# a-star_dual_drv8801_stapler.net
KiCad netlist of a schematic drawn in EAGLE
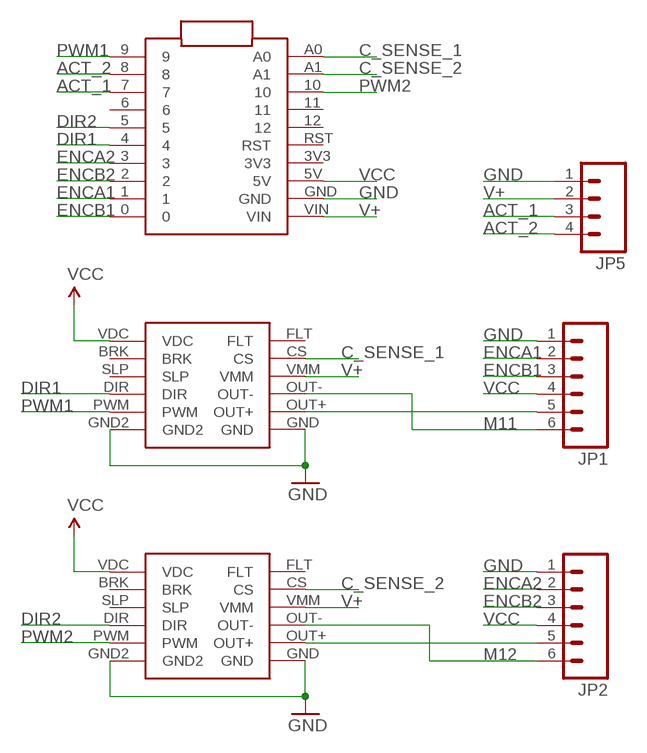
[diagram p0: schematic, sheet 1]

(export (version "E")
  (design (tool "Eeschema 10.0.6"))
  (components
    (comp (ref "JP1")
      (value "M06POLAR")
      (footprint "eagle-import:MOLEX-1X6")
      (libsource (lib "eagle-import") (part "M06POLAR"))
    )
    (comp (ref "JP2")
      (value "M06POLAR")
      (footprint "eagle-import:MOLEX-1X6")
      (libsource (lib "eagle-import") (part "M06POLAR"))
    )
    (comp (ref "JP5")
      (value "M04POLAR")
      (footprint "eagle-import:MOLEX-1X4")
      (libsource (lib "eagle-import") (part "M04POLAR"))
    )
    (comp (ref "U$1")
      (value "POLOLU_DRV8801_CARRIER")
      (footprint "eagle-import:POLOLU_DRV8801_CARRIER")
      (libsource (lib "eagle-import") (part "POLOLU_DRV8801_CARRIER"))
    )
    (comp (ref "U$2")
      (value "POLOLU_A-STAR-MICRO")
      (footprint "eagle-import:POLOLU_A-STAR-MICRO")
      (libsource (lib "eagle-import") (part "POLOLU_A-STAR-MICRO"))
    )
    (comp (ref "U$3")
      (value "POLOLU_DRV8801_CARRIER")
      (footprint "eagle-import:POLOLU_DRV8801_CARRIER")
      (libsource (lib "eagle-import") (part "POLOLU_DRV8801_CARRIER"))
    )
  )
  (nets
    (net (code "1") (name "/ACT_1") (class "Default")
      (node (ref "JP5") (pin "3") (pinfunction "3_3") (pintype "passive"))
      (node (ref "U$2") (pin "7") (pinfunction "7_7") (pintype "bidirectional"))
    )
    (net (code "2") (name "/ACT_2") (class "Default")
      (node (ref "JP5") (pin "4") (pinfunction "4_4") (pintype "passive"))
      (node (ref "U$2") (pin "8") (pinfunction "8_8") (pintype "bidirectional"))
    )
    (net (code "3") (name "/C_SENSE_1") (class "Default")
      (node (ref "U$1") (pin "CS") (pinfunction "CS_CS") (pintype "bidirectional"))
      (node (ref "U$2") (pin "A0") (pinfunction "A0_A0") (pintype "bidirectional"))
    )
    (net (code "4") (name "/C_SENSE_2") (class "Default")
      (node (ref "U$2") (pin "A1") (pinfunction "A1_A1") (pintype "bidirectional"))
      (node (ref "U$3") (pin "CS") (pinfunction "CS_CS") (pintype "bidirectional"))
    )
    (net (code "5") (name "/DIR1") (class "Default")
      (node (ref "U$1") (pin "DIR") (pinfunction "DIR_DIR") (pintype "bidirectional"))
      (node (ref "U$2") (pin "4") (pinfunction "4_4") (pintype "bidirectional"))
    )
    (net (code "6") (name "/DIR2") (class "Default")
      (node (ref "U$2") (pin "5") (pinfunction "5_5") (pintype "bidirectional"))
      (node (ref "U$3") (pin "DIR") (pinfunction "DIR_DIR") (pintype "bidirectional"))
    )
    (net (code "7") (name "/ENCA1") (class "Default")
      (node (ref "JP1") (pin "2") (pinfunction "2_2") (pintype "passive"))
      (node (ref "U$2") (pin "1") (pinfunction "1_1") (pintype "bidirectional"))
    )
    (net (code "8") (name "/ENCA2") (class "Default")
      (node (ref "JP2") (pin "2") (pinfunction "2_2") (pintype "passive"))
      (node (ref "U$2") (pin "3") (pinfunction "3_3") (pintype "bidirectional"))
    )
    (net (code "9") (name "/ENCB1") (class "Default")
      (node (ref "JP1") (pin "3") (pinfunction "3_3") (pintype "passive"))
      (node (ref "U$2") (pin "0") (pinfunction "0_0") (pintype "bidirectional"))
    )
    (net (code "10") (name "/ENCB2") (class "Default")
      (node (ref "JP2") (pin "3") (pinfunction "3_3") (pintype "passive"))
      (node (ref "U$2") (pin "2") (pinfunction "2_2") (pintype "bidirectional"))
    )
    (net (code "11") (name "/M11") (class "Default")
      (node (ref "JP1") (pin "6") (pinfunction "6_6") (pintype "passive"))
      (node (ref "U$1") (pin "OUT-") (pinfunction "OUT-_OUT-") (pintype "bidirectional"))
    )
    (net (code "12") (name "/M12") (class "Default")
      (node (ref "JP2") (pin "6") (pinfunction "6_6") (pintype "passive"))
      (node (ref "U$3") (pin "OUT-") (pinfunction "OUT-_OUT-") (pintype "bidirectional"))
    )
    (net (code "13") (name "/PWM1") (class "Default")
      (node (ref "U$1") (pin "PWM") (pinfunction "PWM_PWM") (pintype "bidirectional"))
      (node (ref "U$2") (pin "9") (pinfunction "9_9") (pintype "bidirectional"))
    )
    (net (code "14") (name "/PWM2") (class "Default")
      (node (ref "U$2") (pin "10") (pinfunction "10_10") (pintype "bidirectional"))
      (node (ref "U$3") (pin "PWM") (pinfunction "PWM_PWM") (pintype "bidirectional"))
    )
    (net (code "15") (name "/V+") (class "Default")
      (node (ref "JP5") (pin "2") (pinfunction "2_2") (pintype "passive"))
      (node (ref "U$1") (pin "VMM") (pinfunction "VMM_VMM") (pintype "bidirectional"))
      (node (ref "U$2") (pin "VIN") (pinfunction "VIN_VIN") (pintype "bidirectional"))
      (node (ref "U$3") (pin "VMM") (pinfunction "VMM_VMM") (pintype "bidirectional"))
    )
    (net (code "16") (name "GND") (class "Default")
      (node (ref "JP1") (pin "1") (pinfunction "1_1") (pintype "passive"))
      (node (ref "JP2") (pin "1") (pinfunction "1_1") (pintype "passive"))
      (node (ref "JP5") (pin "1") (pinfunction "1_1") (pintype "passive"))
      (node (ref "U$1") (pin "GND") (pinfunction "GND_GND") (pintype "bidirectional"))
      (node (ref "U$1") (pin "GND2") (pinfunction "GND2_GND2") (pintype "bidirectional"))
      (node (ref "U$2") (pin "GND") (pinfunction "GND_GND") (pintype "bidirectional"))
      (node (ref "U$3") (pin "GND") (pinfunction "GND_GND") (pintype "bidirectional"))
      (node (ref "U$3") (pin "GND2") (pinfunction "GND2_GND2") (pintype "bidirectional"))
    )
    (net (code "17") (name "Net-(JP1-Pad5)") (class "Default")
      (node (ref "JP1") (pin "5") (pinfunction "5_5") (pintype "passive"))
      (node (ref "U$1") (pin "OUT+") (pinfunction "OUT+_OUT+") (pintype "bidirectional"))
    )
    (net (code "18") (name "Net-(JP2-Pad5)") (class "Default")
      (node (ref "JP2") (pin "5") (pinfunction "5_5") (pintype "passive"))
      (node (ref "U$3") (pin "OUT+") (pinfunction "OUT+_OUT+") (pintype "bidirectional"))
    )
    (net (code "19") (name "VCC") (class "Default")
      (node (ref "JP1") (pin "4") (pinfunction "4_4") (pintype "passive"))
      (node (ref "JP2") (pin "4") (pinfunction "4_4") (pintype "passive"))
      (node (ref "U$1") (pin "VDC") (pinfunction "VDC_VDC") (pintype "bidirectional"))
      (node (ref "U$2") (pin "5V") (pinfunction "5V_5V") (pintype "bidirectional"))
      (node (ref "U$3") (pin "VDC") (pinfunction "VDC_VDC") (pintype "bidirectional"))
    )
    (net (code "20") (name "unconnected-(U$1-PadBRK)") (class "Default")
      (node (ref "U$1") (pin "BRK") (pinfunction "BRK_BRK") (pintype "bidirectional"))
    )
    (net (code "21") (name "unconnected-(U$1-PadFLT)") (class "Default")
      (node (ref "U$1") (pin "FLT") (pinfunction "FLT_FLT") (pintype "bidirectional"))
    )
    (net (code "22") (name "unconnected-(U$1-PadSLP)") (class "Default")
      (node (ref "U$1") (pin "SLP") (pinfunction "SLP_SLP") (pintype "bidirectional"))
    )
    (net (code "23") (name "unconnected-(U$2-Pad3V3)") (class "Default")
      (node (ref "U$2") (pin "3V3") (pinfunction "3V3_3V3") (pintype "bidirectional"))
    )
    (net (code "24") (name "unconnected-(U$2-Pad6)") (class "Default")
      (node (ref "U$2") (pin "6") (pinfunction "6_6") (pintype "bidirectional"))
    )
    (net (code "25") (name "unconnected-(U$2-Pad11)") (class "Default")
      (node (ref "U$2") (pin "11") (pinfunction "11_11") (pintype "bidirectional"))
    )
    (net (code "26") (name "unconnected-(U$2-Pad12)") (class "Default")
      (node (ref "U$2") (pin "12") (pinfunction "12_12") (pintype "bidirectional"))
    )
    (net (code "27") (name "unconnected-(U$2-PadRST)") (class "Default")
      (node (ref "U$2") (pin "RST") (pinfunction "RST_RST") (pintype "bidirectional"))
    )
    (net (code "28") (name "unconnected-(U$3-PadBRK)") (class "Default")
      (node (ref "U$3") (pin "BRK") (pinfunction "BRK_BRK") (pintype "bidirectional"))
    )
    (net (code "29") (name "unconnected-(U$3-PadFLT)") (class "Default")
      (node (ref "U$3") (pin "FLT") (pinfunction "FLT_FLT") (pintype "bidirectional"))
    )
    (net (code "30") (name "unconnected-(U$3-PadSLP)") (class "Default")
      (node (ref "U$3") (pin "SLP") (pinfunction "SLP_SLP") (pintype "bidirectional"))
    )
  )
)
